# mainboard_200305.net
KiCad netlist of a schematic drawn in EAGLE
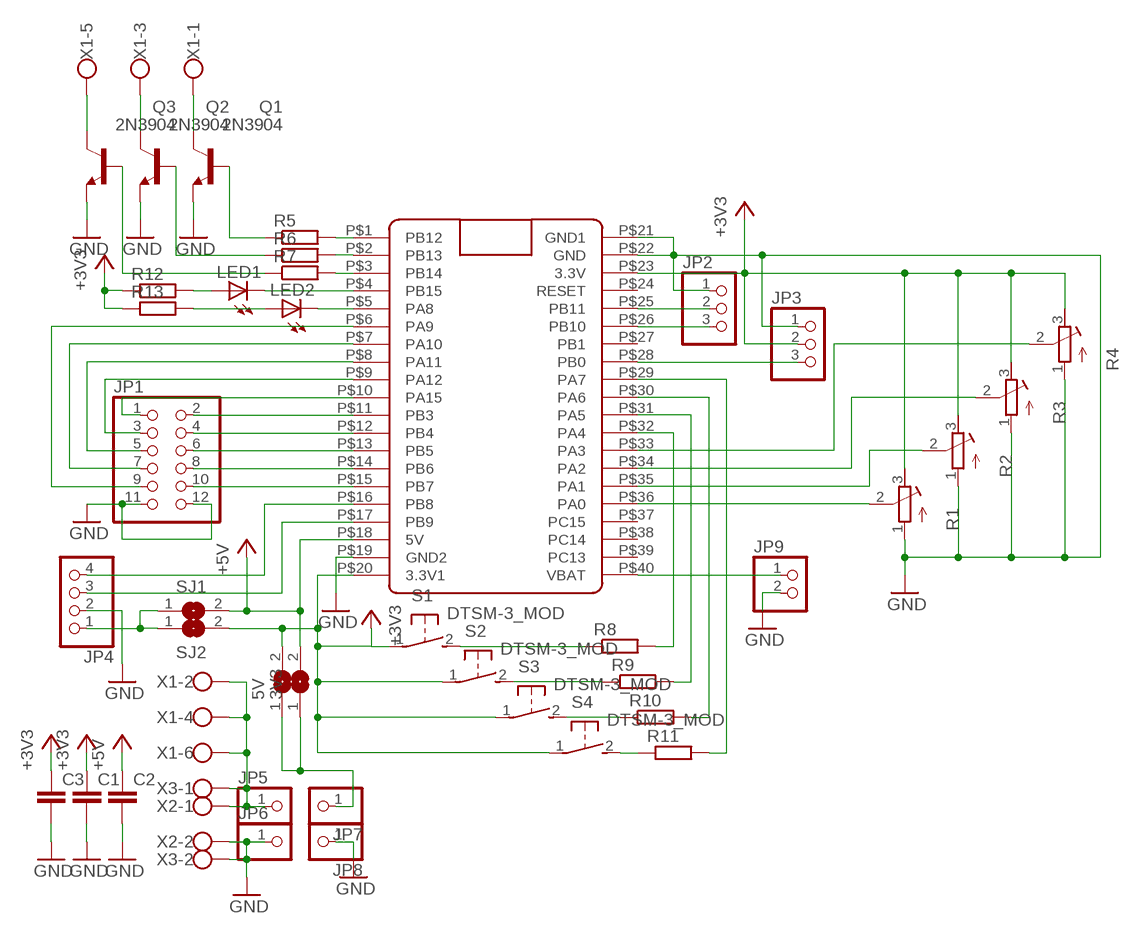
[diagram p0: schematic, sheet 1]

(export (version "E")
  (design (tool "Eeschema 10.0.6"))
  (components
    (comp (ref "3V3") (value "SJ") (footprint "eagle-import:SJ") (libsource (lib "eagle-import") (part "SJ")))
    (comp (ref "5V") (value "SJ") (footprint "eagle-import:SJ") (libsource (lib "eagle-import") (part "SJ")))
    (comp (ref "C1")
      (value "C-EU050-045X075")
      (footprint "eagle-import:C050-045X075")
      (libsource (lib "eagle-import") (part "C-EU050-045X075"))
    )
    (comp (ref "C2")
      (value "C-EU050-045X075")
      (footprint "eagle-import:C050-045X075")
      (libsource (lib "eagle-import") (part "C-EU050-045X075"))
    )
    (comp (ref "C3")
      (value "C-EU050-045X075")
      (footprint "eagle-import:C050-045X075")
      (libsource (lib "eagle-import") (part "C-EU050-045X075"))
    )
    (comp (ref "JP1")
      (value "PINHD-2X6")
      (footprint "eagle-import:2X06")
      (libsource (lib "eagle-import") (part "PINHD-2X6"))
    )
    (comp (ref "JP2")
      (value "PINHD-1X3")
      (footprint "eagle-import:1X03")
      (libsource (lib "eagle-import") (part "PINHD-1X3"))
    )
    (comp (ref "JP3")
      (value "PINHD-1X3")
      (footprint "eagle-import:1X03")
      (libsource (lib "eagle-import") (part "PINHD-1X3"))
    )
    (comp (ref "JP4")
      (value "PINHD-1X4")
      (footprint "eagle-import:1X04")
      (libsource (lib "eagle-import") (part "PINHD-1X4"))
    )
    (comp (ref "JP5")
      (value "PINHD-1X1")
      (footprint "eagle-import:1X01")
      (libsource (lib "eagle-import") (part "PINHD-1X1"))
    )
    (comp (ref "JP6")
      (value "PINHD-1X1")
      (footprint "eagle-import:1X01")
      (libsource (lib "eagle-import") (part "PINHD-1X1"))
    )
    (comp (ref "JP7")
      (value "PINHD-1X1")
      (footprint "eagle-import:1X01")
      (libsource (lib "eagle-import") (part "PINHD-1X1"))
    )
    (comp (ref "JP8")
      (value "PINHD-1X1")
      (footprint "eagle-import:1X01")
      (libsource (lib "eagle-import") (part "PINHD-1X1"))
    )
    (comp (ref "JP9")
      (value "PINHD-1X2")
      (footprint "eagle-import:1X02")
      (libsource (lib "eagle-import") (part "PINHD-1X2"))
    )
    (comp (ref "LED1")
      (value "LEDCHIPLED_1206")
      (footprint "eagle-import:CHIPLED_1206")
      (libsource (lib "eagle-import") (part "LEDCHIPLED_1206"))
    )
    (comp (ref "LED2")
      (value "LEDCHIPLED_1206")
      (footprint "eagle-import:CHIPLED_1206")
      (libsource (lib "eagle-import") (part "LEDCHIPLED_1206"))
    )
    (comp (ref "Q1")
      (value "2N3904")
      (footprint "eagle-import:TO92")
      (libsource (lib "eagle-import") (part "2N3904"))
    )
    (comp (ref "Q2")
      (value "2N3904")
      (footprint "eagle-import:TO92")
      (libsource (lib "eagle-import") (part "2N3904"))
    )
    (comp (ref "Q3")
      (value "2N3904")
      (footprint "eagle-import:TO92")
      (libsource (lib "eagle-import") (part "2N3904"))
    )
    (comp (ref "R1")
      (value "R-TRIMM64W")
      (footprint "eagle-import:RTRIM64W")
      (libsource (lib "eagle-import") (part "R-TRIMM64W"))
    )
    (comp (ref "R2")
      (value "R-TRIMM64W")
      (footprint "eagle-import:RTRIM64W")
      (libsource (lib "eagle-import") (part "R-TRIMM64W"))
    )
    (comp (ref "R3")
      (value "R-TRIMM64W")
      (footprint "eagle-import:RTRIM64W")
      (libsource (lib "eagle-import") (part "R-TRIMM64W"))
    )
    (comp (ref "R4")
      (value "R-TRIMM64W")
      (footprint "eagle-import:RTRIM64W")
      (libsource (lib "eagle-import") (part "R-TRIMM64W"))
    )
    (comp (ref "R5")
      (value "R-EU_R1206")
      (footprint "eagle-import:R1206")
      (libsource (lib "eagle-import") (part "R-EU_R1206"))
    )
    (comp (ref "R6")
      (value "R-EU_R1206")
      (footprint "eagle-import:R1206")
      (libsource (lib "eagle-import") (part "R-EU_R1206"))
    )
    (comp (ref "R7")
      (value "R-EU_R1206")
      (footprint "eagle-import:R1206")
      (libsource (lib "eagle-import") (part "R-EU_R1206"))
    )
    (comp (ref "R8")
      (value "R-EU_R1206")
      (footprint "eagle-import:R1206")
      (libsource (lib "eagle-import") (part "R-EU_R1206"))
    )
    (comp (ref "R9")
      (value "R-EU_R1206")
      (footprint "eagle-import:R1206")
      (libsource (lib "eagle-import") (part "R-EU_R1206"))
    )
    (comp (ref "R10")
      (value "R-EU_R1206")
      (footprint "eagle-import:R1206")
      (libsource (lib "eagle-import") (part "R-EU_R1206"))
    )
    (comp (ref "R11")
      (value "R-EU_R1206")
      (footprint "eagle-import:R1206")
      (libsource (lib "eagle-import") (part "R-EU_R1206"))
    )
    (comp (ref "R12")
      (value "R-EU_R1206")
      (footprint "eagle-import:R1206")
      (libsource (lib "eagle-import") (part "R-EU_R1206"))
    )
    (comp (ref "R13")
      (value "R-EU_R1206")
      (footprint "eagle-import:R1206")
      (libsource (lib "eagle-import") (part "R-EU_R1206"))
    )
    (comp (ref "S1")
      (value "DTSM-3_MOD")
      (footprint "eagle-import:DTSM-3_MOD")
      (libsource (lib "eagle-import") (part "DTSM-3_MOD"))
    )
    (comp (ref "S2")
      (value "DTSM-3_MOD")
      (footprint "eagle-import:DTSM-3_MOD")
      (libsource (lib "eagle-import") (part "DTSM-3_MOD"))
    )
    (comp (ref "S3")
      (value "DTSM-3_MOD")
      (footprint "eagle-import:DTSM-3_MOD")
      (libsource (lib "eagle-import") (part "DTSM-3_MOD"))
    )
    (comp (ref "S4")
      (value "DTSM-3_MOD")
      (footprint "eagle-import:DTSM-3_MOD")
      (libsource (lib "eagle-import") (part "DTSM-3_MOD"))
    )
    (comp (ref "SJ1") (value "SJ") (footprint "eagle-import:SJ") (libsource (lib "eagle-import") (part "SJ")))
    (comp (ref "SJ2") (value "SJ") (footprint "eagle-import:SJ") (libsource (lib "eagle-import") (part "SJ")))
    (comp (ref "U$1")
      (value "BLUE_PILL")
      (footprint "eagle-import:BLUE_PILL")
      (libsource (lib "eagle-import") (part "BLUE_PILL"))
    )
    (comp (ref "X1")
      (value "W237-6")
      (footprint "eagle-import:W237-6")
      (libsource (lib "eagle-import") (part "W237-6"))
    )
    (comp (ref "X2")
      (value "W237-102")
      (footprint "eagle-import:W237-102")
      (fields (field (name "MPN") "237-102"))
      (libsource (lib "eagle-import") (part "W237-102"))
    )
    (comp (ref "X3")
      (value "W237-102")
      (footprint "eagle-import:W237-102")
      (fields (field (name "MPN") "237-102"))
      (libsource (lib "eagle-import") (part "W237-102"))
    )
  )
  (nets
    (net (code "1") (name "+3V3") (class "Default")
      (node (ref "5V") (pin "2") (pinfunction "2_2") (pintype "passive"))
      (node (ref "C1") (pin "1") (pinfunction "1_1") (pintype "passive"))
      (node (ref "C3") (pin "1") (pinfunction "1_1") (pintype "passive"))
      (node (ref "JP3") (pin "2") (pinfunction "2_2") (pintype "passive"))
      (node (ref "R1") (pin "3") (pinfunction "E_3") (pintype "passive"))
      (node (ref "R12") (pin "1") (pinfunction "1_1") (pintype "passive"))
      (node (ref "R13") (pin "1") (pinfunction "1_1") (pintype "passive"))
      (node (ref "R2") (pin "3") (pinfunction "E_3") (pintype "passive"))
      (node (ref "R3") (pin "3") (pinfunction "E_3") (pintype "passive"))
      (node (ref "R4") (pin "3") (pinfunction "E_3") (pintype "passive"))
      (node (ref "S1") (pin "1") (pinfunction "1_1") (pintype "passive"))
      (node (ref "S2") (pin "1") (pinfunction "1_1") (pintype "passive"))
      (node (ref "S3") (pin "1") (pinfunction "1_1") (pintype "passive"))
      (node (ref "S4") (pin "1") (pinfunction "1_1") (pintype "passive"))
      (node (ref "SJ2") (pin "2") (pinfunction "2_2") (pintype "passive"))
      (node (ref "U$1") (pin "P$20") (pinfunction "3.3V1_P$20") (pintype "bidirectional"))
      (node (ref "U$1") (pin "P$23") (pinfunction "3.3V_P$23") (pintype "bidirectional"))
    )
    (net (code "2") (name "+5V") (class "Default")
      (node (ref "3V3") (pin "2") (pinfunction "2_2") (pintype "passive"))
      (node (ref "C2") (pin "1") (pinfunction "1_1") (pintype "passive"))
      (node (ref "SJ1") (pin "2") (pinfunction "2_2") (pintype "passive"))
      (node (ref "U$1") (pin "P$18") (pinfunction "5V_P$18") (pintype "bidirectional"))
    )
    (net (code "3") (name "GND") (class "Default")
      (node (ref "C1") (pin "2") (pinfunction "2_2") (pintype "passive"))
      (node (ref "C2") (pin "2") (pinfunction "2_2") (pintype "passive"))
      (node (ref "C3") (pin "2") (pinfunction "2_2") (pintype "passive"))
      (node (ref "JP1") (pin "11") (pinfunction "11_11") (pintype "passive"))
      (node (ref "JP1") (pin "12") (pinfunction "12_12") (pintype "passive"))
      (node (ref "JP2") (pin "1") (pinfunction "1_1") (pintype "passive"))
      (node (ref "JP3") (pin "1") (pinfunction "1_1") (pintype "passive"))
      (node (ref "JP4") (pin "2") (pinfunction "2_2") (pintype "passive"))
      (node (ref "JP6") (pin "1") (pinfunction "1_1") (pintype "passive"))
      (node (ref "JP8") (pin "1") (pinfunction "1_1") (pintype "passive"))
      (node (ref "JP9") (pin "2") (pinfunction "2_2") (pintype "passive"))
      (node (ref "Q1") (pin "3") (pinfunction "E_3") (pintype "passive"))
      (node (ref "Q2") (pin "3") (pinfunction "E_3") (pintype "passive"))
      (node (ref "Q3") (pin "3") (pinfunction "E_3") (pintype "passive"))
      (node (ref "R1") (pin "1") (pinfunction "A_1") (pintype "passive"))
      (node (ref "R2") (pin "1") (pinfunction "A_1") (pintype "passive"))
      (node (ref "R3") (pin "1") (pinfunction "A_1") (pintype "passive"))
      (node (ref "R4") (pin "1") (pinfunction "A_1") (pintype "passive"))
      (node (ref "U$1") (pin "P$19") (pinfunction "GND2_P$19") (pintype "bidirectional"))
      (node (ref "U$1") (pin "P$21") (pinfunction "GND1_P$21") (pintype "power_in"))
      (node (ref "U$1") (pin "P$22") (pinfunction "GND_P$22") (pintype "bidirectional"))
      (node (ref "X2") (pin "2") (pinfunction "KL_2") (pintype "passive"))
      (node (ref "X3") (pin "2") (pinfunction "KL_2") (pintype "passive"))
    )
    (net (code "4") (name "Net-(3V3-Pad1)") (class "Default")
      (node (ref "3V3") (pin "1") (pinfunction "1_1") (pintype "passive"))
      (node (ref "5V") (pin "1") (pinfunction "1_1") (pintype "passive"))
      (node (ref "JP7") (pin "1") (pinfunction "1_1") (pintype "passive"))
    )
    (net (code "5") (name "Net-(JP4-Pad1)") (class "Default")
      (node (ref "JP4") (pin "1") (pinfunction "1_1") (pintype "passive"))
      (node (ref "SJ1") (pin "1") (pinfunction "1_1") (pintype "passive"))
      (node (ref "SJ2") (pin "1") (pinfunction "1_1") (pintype "passive"))
    )
    (net (code "6") (name "Net-(LED1-PadA)") (class "Default")
      (node (ref "LED1") (pin "A") (pinfunction "A_A") (pintype "passive"))
      (node (ref "R12") (pin "2") (pinfunction "2_2") (pintype "passive"))
    )
    (net (code "7") (name "Net-(LED2-PadA)") (class "Default")
      (node (ref "LED2") (pin "A") (pinfunction "A_A") (pintype "passive"))
      (node (ref "R13") (pin "2") (pinfunction "2_2") (pintype "passive"))
    )
    (net (code "8") (name "Net-(Q1-B)") (class "Default")
      (node (ref "Q1") (pin "2") (pinfunction "B_2") (pintype "passive"))
      (node (ref "R5") (pin "1") (pinfunction "1_1") (pintype "passive"))
    )
    (net (code "9") (name "Net-(Q1-C)") (class "Default")
      (node (ref "Q1") (pin "1") (pinfunction "C_1") (pintype "passive"))
      (node (ref "X1") (pin "1") (pinfunction "KL_1") (pintype "passive"))
    )
    (net (code "10") (name "Net-(Q2-B)") (class "Default")
      (node (ref "Q2") (pin "2") (pinfunction "B_2") (pintype "passive"))
      (node (ref "R6") (pin "1") (pinfunction "1_1") (pintype "passive"))
    )
    (net (code "11") (name "Net-(Q2-C)") (class "Default")
      (node (ref "Q2") (pin "1") (pinfunction "C_1") (pintype "passive"))
      (node (ref "X1") (pin "3") (pinfunction "KL_3") (pintype "passive"))
    )
    (net (code "12") (name "Net-(Q3-B)") (class "Default")
      (node (ref "Q3") (pin "2") (pinfunction "B_2") (pintype "passive"))
      (node (ref "R7") (pin "1") (pinfunction "1_1") (pintype "passive"))
    )
    (net (code "13") (name "Net-(Q3-C)") (class "Default")
      (node (ref "Q3") (pin "1") (pinfunction "C_1") (pintype "passive"))
      (node (ref "X1") (pin "5") (pinfunction "KL_5") (pintype "passive"))
    )
    (net (code "14") (name "Net-(R1-S)") (class "Default")
      (node (ref "R1") (pin "2") (pinfunction "S_2") (pintype "passive"))
      (node (ref "U$1") (pin "P$36") (pinfunction "PA0_P$36") (pintype "bidirectional"))
    )
    (net (code "15") (name "Net-(R2-S)") (class "Default")
      (node (ref "R2") (pin "2") (pinfunction "S_2") (pintype "passive"))
      (node (ref "U$1") (pin "P$35") (pinfunction "PA1_P$35") (pintype "bidirectional"))
    )
    (net (code "16") (name "Net-(R3-S)") (class "Default")
      (node (ref "R3") (pin "2") (pinfunction "S_2") (pintype "passive"))
      (node (ref "U$1") (pin "P$34") (pinfunction "PA2_P$34") (pintype "bidirectional"))
    )
    (net (code "17") (name "Net-(R4-S)") (class "Default")
      (node (ref "R4") (pin "2") (pinfunction "S_2") (pintype "passive"))
      (node (ref "U$1") (pin "P$33") (pinfunction "PA3_P$33") (pintype "bidirectional"))
    )
    (net (code "18") (name "Net-(R8-Pad1)") (class "Default")
      (node (ref "R8") (pin "1") (pinfunction "1_1") (pintype "passive"))
      (node (ref "S1") (pin "2") (pinfunction "2_2") (pintype "passive"))
    )
    (net (code "19") (name "Net-(R9-Pad1)") (class "Default")
      (node (ref "R9") (pin "1") (pinfunction "1_1") (pintype "passive"))
      (node (ref "S2") (pin "2") (pinfunction "2_2") (pintype "passive"))
    )
    (net (code "20") (name "Net-(R10-Pad1)") (class "Default")
      (node (ref "R10") (pin "1") (pinfunction "1_1") (pintype "passive"))
      (node (ref "S3") (pin "2") (pinfunction "2_2") (pintype "passive"))
    )
    (net (code "21") (name "Net-(R11-Pad1)") (class "Default")
      (node (ref "R11") (pin "1") (pinfunction "1_1") (pintype "passive"))
      (node (ref "S4") (pin "2") (pinfunction "2_2") (pintype "passive"))
    )
    (net (code "22") (name "Net-(U$1-PA4)") (class "Default")
      (node (ref "R8") (pin "2") (pinfunction "2_2") (pintype "passive"))
      (node (ref "U$1") (pin "P$32") (pinfunction "PA4_P$32") (pintype "bidirectional"))
    )
    (net (code "23") (name "Net-(U$1-PA5)") (class "Default")
      (node (ref "R9") (pin "2") (pinfunction "2_2") (pintype "passive"))
      (node (ref "U$1") (pin "P$31") (pinfunction "PA5_P$31") (pintype "bidirectional"))
    )
    (net (code "24") (name "Net-(U$1-PA6)") (class "Default")
      (node (ref "R10") (pin "2") (pinfunction "2_2") (pintype "passive"))
      (node (ref "U$1") (pin "P$30") (pinfunction "PA6_P$30") (pintype "bidirectional"))
    )
    (net (code "25") (name "Net-(U$1-PA7)") (class "Default")
      (node (ref "R11") (pin "2") (pinfunction "2_2") (pintype "passive"))
      (node (ref "U$1") (pin "P$29") (pinfunction "PA7_P$29") (pintype "bidirectional"))
    )
    (net (code "26") (name "Net-(U$1-PA8)") (class "Default")
      (node (ref "LED2") (pin "C") (pinfunction "C_C") (pintype "passive"))
      (node (ref "U$1") (pin "P$5") (pinfunction "PA8_P$5") (pintype "bidirectional"))
    )
    (net (code "27") (name "Net-(U$1-PA9)") (class "Default")
      (node (ref "JP1") (pin "9") (pinfunction "9_9") (pintype "passive"))
      (node (ref "U$1") (pin "P$6") (pinfunction "PA9_P$6") (pintype "bidirectional"))
    )
    (net (code "28") (name "Net-(U$1-PA10)") (class "Default")
      (node (ref "JP1") (pin "7") (pinfunction "7_7") (pintype "passive"))
      (node (ref "U$1") (pin "P$7") (pinfunction "PA10_P$7") (pintype "bidirectional"))
    )
    (net (code "29") (name "Net-(U$1-PA11)") (class "Default")
      (node (ref "JP1") (pin "5") (pinfunction "5_5") (pintype "passive"))
      (node (ref "U$1") (pin "P$8") (pinfunction "PA11_P$8") (pintype "bidirectional"))
    )
    (net (code "30") (name "Net-(U$1-PA12)") (class "Default")
      (node (ref "JP1") (pin "3") (pinfunction "3_3") (pintype "passive"))
      (node (ref "U$1") (pin "P$9") (pinfunction "PA12_P$9") (pintype "bidirectional"))
    )
    (net (code "31") (name "Net-(U$1-PA15)") (class "Default")
      (node (ref "JP1") (pin "1") (pinfunction "1_1") (pintype "passive"))
      (node (ref "U$1") (pin "P$10") (pinfunction "PA15_P$10") (pintype "bidirectional"))
    )
    (net (code "32") (name "Net-(U$1-PB0)") (class "Default")
      (node (ref "JP3") (pin "3") (pinfunction "3_3") (pintype "passive"))
      (node (ref "U$1") (pin "P$28") (pinfunction "PB0_P$28") (pintype "bidirectional"))
    )
    (net (code "33") (name "Net-(U$1-PB3)") (class "Default")
      (node (ref "JP1") (pin "2") (pinfunction "2_2") (pintype "passive"))
      (node (ref "U$1") (pin "P$11") (pinfunction "PB3_P$11") (pintype "bidirectional"))
    )
    (net (code "34") (name "Net-(U$1-PB4)") (class "Default")
      (node (ref "JP1") (pin "4") (pinfunction "4_4") (pintype "passive"))
      (node (ref "U$1") (pin "P$12") (pinfunction "PB4_P$12") (pintype "bidirectional"))
    )
    (net (code "35") (name "Net-(U$1-PB5)") (class "Default")
      (node (ref "JP1") (pin "6") (pinfunction "6_6") (pintype "passive"))
      (node (ref "U$1") (pin "P$13") (pinfunction "PB5_P$13") (pintype "bidirectional"))
    )
    (net (code "36") (name "Net-(U$1-PB6)") (class "Default")
      (node (ref "JP1") (pin "8") (pinfunction "8_8") (pintype "passive"))
      (node (ref "U$1") (pin "P$14") (pinfunction "PB6_P$14") (pintype "bidirectional"))
    )
    (net (code "37") (name "Net-(U$1-PB7)") (class "Default")
      (node (ref "JP1") (pin "10") (pinfunction "10_10") (pintype "passive"))
      (node (ref "U$1") (pin "P$15") (pinfunction "PB7_P$15") (pintype "bidirectional"))
    )
    (net (code "38") (name "Net-(U$1-PB8)") (class "Default")
      (node (ref "JP4") (pin "4") (pinfunction "4_4") (pintype "passive"))
      (node (ref "U$1") (pin "P$16") (pinfunction "PB8_P$16") (pintype "bidirectional"))
    )
    (net (code "39") (name "Net-(U$1-PB9)") (class "Default")
      (node (ref "JP4") (pin "3") (pinfunction "3_3") (pintype "passive"))
      (node (ref "U$1") (pin "P$17") (pinfunction "PB9_P$17") (pintype "bidirectional"))
    )
    (net (code "40") (name "Net-(U$1-PB10)") (class "Default")
      (node (ref "JP2") (pin "3") (pinfunction "3_3") (pintype "passive"))
      (node (ref "U$1") (pin "P$26") (pinfunction "PB10_P$26") (pintype "bidirectional"))
    )
    (net (code "41") (name "Net-(U$1-PB11)") (class "Default")
      (node (ref "JP2") (pin "2") (pinfunction "2_2") (pintype "passive"))
      (node (ref "U$1") (pin "P$25") (pinfunction "PB11_P$25") (pintype "bidirectional"))
    )
    (net (code "42") (name "Net-(U$1-PB12)") (class "Default")
      (node (ref "R5") (pin "2") (pinfunction "2_2") (pintype "passive"))
      (node (ref "U$1") (pin "P$1") (pinfunction "PB12_P$1") (pintype "bidirectional"))
    )
    (net (code "43") (name "Net-(U$1-PB13)") (class "Default")
      (node (ref "R6") (pin "2") (pinfunction "2_2") (pintype "passive"))
      (node (ref "U$1") (pin "P$2") (pinfunction "PB13_P$2") (pintype "bidirectional"))
    )
    (net (code "44") (name "Net-(U$1-PB14)") (class "Default")
      (node (ref "R7") (pin "2") (pinfunction "2_2") (pintype "passive"))
      (node (ref "U$1") (pin "P$3") (pinfunction "PB14_P$3") (pintype "bidirectional"))
    )
    (net (code "45") (name "Net-(U$1-PB15)") (class "Default")
      (node (ref "LED1") (pin "C") (pinfunction "C_C") (pintype "passive"))
      (node (ref "U$1") (pin "P$4") (pinfunction "PB15_P$4") (pintype "bidirectional"))
    )
    (net (code "46") (name "Net-(U$1-VBAT)") (class "Default")
      (node (ref "JP9") (pin "1") (pinfunction "1_1") (pintype "passive"))
      (node (ref "U$1") (pin "P$40") (pinfunction "VBAT_P$40") (pintype "bidirectional"))
    )
    (net (code "47") (name "Net-(X1B-KL)") (class "Default")
      (node (ref "JP5") (pin "1") (pinfunction "1_1") (pintype "passive"))
      (node (ref "X1") (pin "2") (pinfunction "KL_2") (pintype "passive"))
      (node (ref "X1") (pin "4") (pinfunction "KL_4") (pintype "passive"))
      (node (ref "X1") (pin "6") (pinfunction "KL_6") (pintype "passive"))
      (node (ref "X2") (pin "1") (pinfunction "KL_1") (pintype "passive"))
      (node (ref "X3") (pin "1") (pinfunction "KL_1") (pintype "passive"))
    )
    (net (code "48") (name "unconnected-(U$1-PB1-PadP$27)") (class "Default")
      (node (ref "U$1") (pin "P$27") (pinfunction "PB1_P$27") (pintype "bidirectional"))
    )
    (net (code "49") (name "unconnected-(U$1-PC13-PadP$39)") (class "Default")
      (node (ref "U$1") (pin "P$39") (pinfunction "PC13_P$39") (pintype "bidirectional"))
    )
    (net (code "50") (name "unconnected-(U$1-PC14-PadP$38)") (class "Default")
      (node (ref "U$1") (pin "P$38") (pinfunction "PC14_P$38") (pintype "bidirectional"))
    )
    (net (code "51") (name "unconnected-(U$1-PC15-PadP$37)") (class "Default")
      (node (ref "U$1") (pin "P$37") (pinfunction "PC15_P$37") (pintype "bidirectional"))
    )
    (net (code "52") (name "unconnected-(U$1-RESET-PadP$24)") (class "Default")
      (node (ref "U$1") (pin "P$24") (pinfunction "RESET_P$24") (pintype "bidirectional"))
    )
  )
)
